# MOTOR.net
KiCad netlist of a schematic drawn in Altium Designer
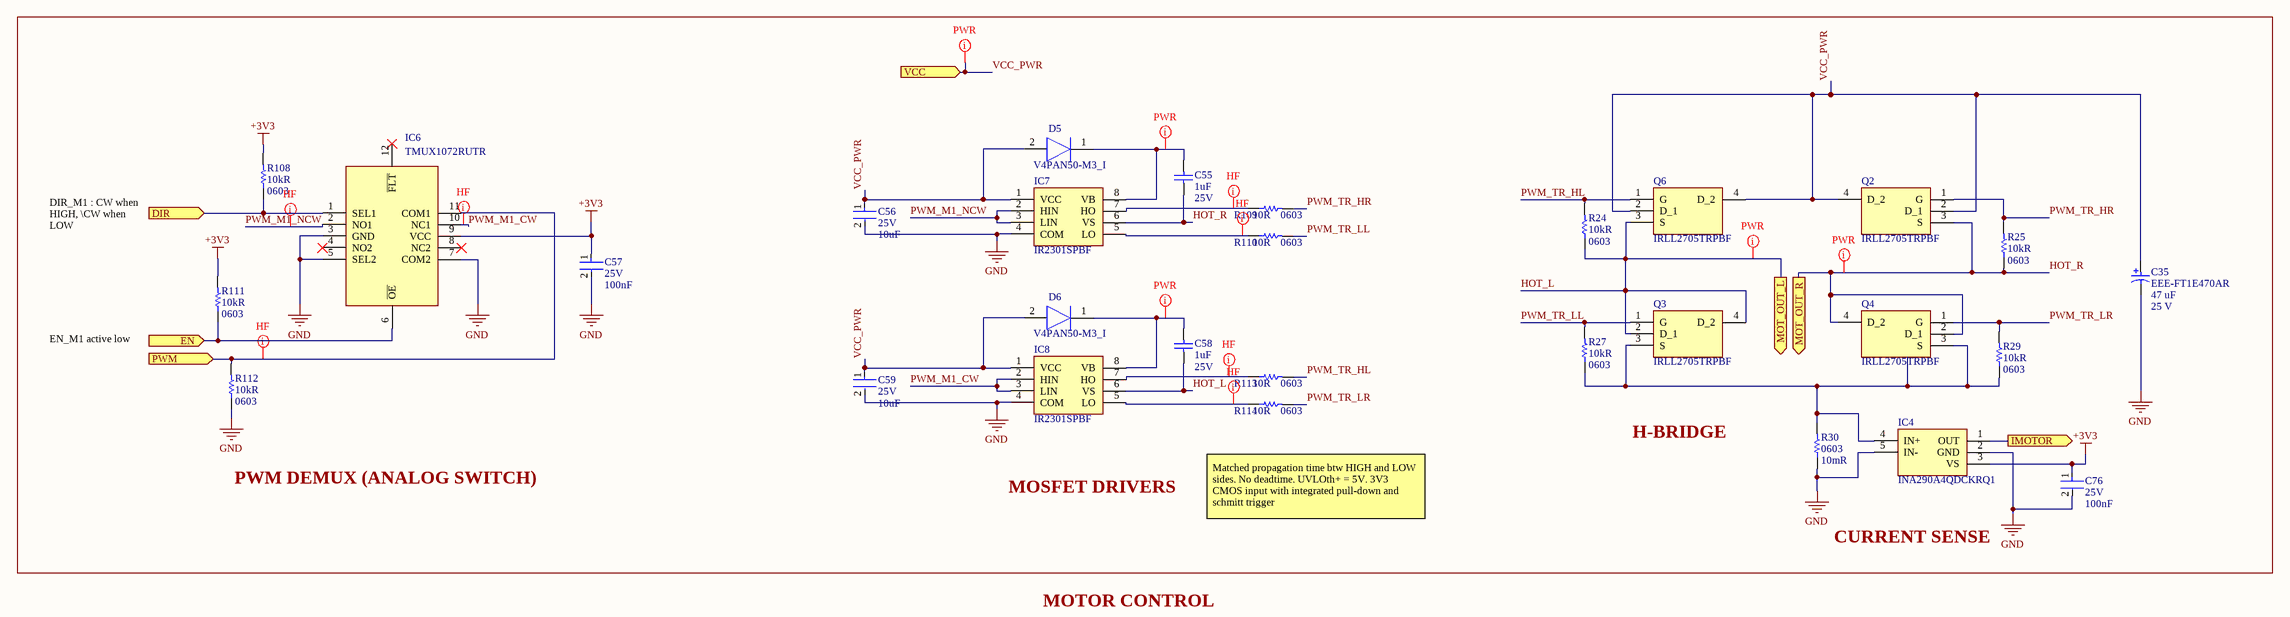
[diagram p0: MOTOR.SchDoc]

(export (version "E")
  (design (tool "Eeschema 10.0.6"))
  (components
    (comp (ref "C35")
      (value "EEE-FT1E470AR")
      (footprint "PNSC-FT-V-53x53-2_V")
      (fields
        (field (name "CAP.") "47 uF")
        (field (name "MANUFACTURER") "Panasonic")
        (field (name "RATED VOLTAGE") "25 V")
      )
      (libsource (lib "Altium Content Vault") (part "PNSC-CAP-P-2"))
    )
    (comp (ref "C55")
      (value "C0603C105K3PAC7867")
      (footprint "CAPC1608X90X35LL15T15")
      (fields
        (field (name "MANUFACTURER") "Kemet")
        (field (name "MANUFACTURER PART NUMBER") "C0603C105K3PACTU")
        (field (name "CAPACITANCE") "1uF")
        (field (name "TOLERANCE") "10%")
        (field (name "VOLTAGE RATING (DC)") "25V")
      )
      (libsource (lib "Altium Content Vault") (part "CAP"))
    )
    (comp (ref "C56")
      (value "C2012X5R1E106K125AB")
      (footprint "FP-C2012-125-0_2-IPC_B")
      (description "Multilayer Ceramic Capacitors 10μF ±10% 25V X5R SMD 0805")
      (fields
        (field (name "VOLTAGE") "25V")
        (field (name "VOLTAGE RATING (DC)") "25V")
        (field (name "TOLERANCE") "10%")
        (field (name "CAPACITANCE") "10uF")
      )
      (libsource (lib "Altium Content Vault") (part "b4654b650e69147ec39a6b967a45e02"))
    )
    (comp (ref "C57")
      (value "CGA3E2X7R1E104K080AA")
      (footprint "FP-CGA3E-0_3-0_1-MFG")
      (description "Cap Ceramic 100nF 25V X7R 10% Pad SMD 0603 +125°C Automotive T/R")
      (fields
        (field (name "VOLTAGE RATING (DC)") "25V")
        (field (name "CAPACITANCE") "100nF")
        (field (name "TOLERANCE") "10%")
        (field (name "MANUFACTURER") "TDK")
      )
      (libsource (lib "Altium Content Vault") (part "b4654b650e69147ec39a6b967a45e02"))
    )
    (comp (ref "C58")
      (value "C0603C105K3PAC7867")
      (footprint "CAPC1608X90X35LL15T15")
      (fields
        (field (name "MANUFACTURER") "Kemet")
        (field (name "MANUFACTURER PART NUMBER") "C0603C105K3PACTU")
        (field (name "CAPACITANCE") "1uF")
        (field (name "TOLERANCE") "10%")
        (field (name "VOLTAGE RATING (DC)") "25V")
      )
      (libsource (lib "Altium Content Vault") (part "CAP"))
    )
    (comp (ref "C59")
      (value "C2012X5R1E106K125AB")
      (footprint "FP-C2012-125-0_2-IPC_B")
      (description "Multilayer Ceramic Capacitors 10μF ±10% 25V X5R SMD 0805")
      (fields
        (field (name "VOLTAGE") "25V")
        (field (name "VOLTAGE RATING (DC)") "25V")
        (field (name "TOLERANCE") "10%")
        (field (name "CAPACITANCE") "10uF")
      )
      (libsource (lib "Altium Content Vault") (part "b4654b650e69147ec39a6b967a45e02"))
    )
    (comp (ref "C76")
      (value "CGA3E2X7R1E104K080AA")
      (footprint "FP-CGA3E-0_3-0_1-MFG")
      (description "Cap Ceramic 100nF 25V X7R 10% Pad SMD 0603 +125°C Automotive T/R")
      (fields
        (field (name "VOLTAGE RATING (DC)") "25V")
        (field (name "CAPACITANCE") "100nF")
        (field (name "TOLERANCE") "10%")
        (field (name "MANUFACTURER") "TDK")
      )
      (libsource (lib "Altium Content Vault") (part "b4654b650e69147ec39a6b967a45e02"))
    )
    (comp (ref "D5")
      (value "V4PAN50-M3_I")
      (footprint "SamacSys:V4PAN50M3I")
      (description "Diode")
      (fields
        (field (name "MANUFACTURER_PART_NUMBER") "V4PAN50-M3/I")
        (field (name "MOUSER PART NUMBER") "78-V4PAN50-M3/I")
      )
      (libsource (lib "*") (part "V4PAN50-M3_I"))
    )
    (comp (ref "D6")
      (value "V4PAN50-M3_I")
      (footprint "SamacSys:V4PAN50M3I")
      (description "Diode")
      (fields
        (field (name "MANUFACTURER_PART_NUMBER") "V4PAN50-M3/I")
        (field (name "MOUSER PART NUMBER") "78-V4PAN50-M3/I")
      )
      (libsource (lib "*") (part "V4PAN50-M3_I"))
    )
    (comp (ref "IC4")
      (value "INA290A4QDCKRQ1")
      (footprint "SamacSys:SOT65P210X110-5N")
      (description "Integrated Circuit")
      (fields (field (name "MOUSER PART NUMBER") "595-INA290A4QDCKRQ1"))
      (libsource (lib "*") (part "INA290A4QDCKRQ1"))
    )
    (comp (ref "IC6")
      (value "TMUX1072RUTR")
      (footprint "SamacSys:QFN40P170X200X55-12N")
      (description "Integrated Circuit")
      (fields (field (name "MOUSER PART NUMBER") "595-TMUX1072RUTR"))
      (libsource (lib "*") (part "TMUX1072RUTR"))
    )
    (comp (ref "IC7")
      (value "IR2301SPBF")
      (footprint "SamacSys:SOIC127P600X175-8N")
      (description "Integrated Circuit")
      (fields (field (name "MOUSER PART NUMBER") "942-IR2301SPBF"))
      (libsource (lib "*") (part "IR2301SPBF"))
    )
    (comp (ref "IC8")
      (value "IR2301SPBF")
      (footprint "SamacSys:SOIC127P600X175-8N")
      (description "Integrated Circuit")
      (fields (field (name "MOUSER PART NUMBER") "942-IR2301SPBF"))
      (libsource (lib "*") (part "IR2301SPBF"))
    )
    (comp (ref "Q2")
      (value "IRLL2705TRPBF")
      (footprint "SamacSys:SOT230P700X180-4N")
      (description "MOSFET (N-Channel)")
      (fields (field (name "MOUSER PART NUMBER") "942-IRLL2705TRPBF"))
      (libsource (lib "") (part "IRLL2705TRPBF_1"))
    )
    (comp (ref "Q3")
      (value "IRLL2705TRPBF")
      (footprint "SamacSys:SOT230P700X180-4N")
      (description "MOSFET (N-Channel)")
      (fields (field (name "MOUSER PART NUMBER") "942-IRLL2705TRPBF"))
      (libsource (lib "*") (part "IRLL2705TRPBF"))
    )
    (comp (ref "Q4")
      (value "IRLL2705TRPBF")
      (footprint "SamacSys:SOT230P700X180-4N")
      (description "MOSFET (N-Channel)")
      (fields (field (name "MOUSER PART NUMBER") "942-IRLL2705TRPBF"))
      (libsource (lib "") (part "IRLL2705TRPBF_1"))
    )
    (comp (ref "Q6")
      (value "IRLL2705TRPBF")
      (footprint "SamacSys:SOT230P700X180-4N")
      (description "MOSFET (N-Channel)")
      (fields (field (name "MOUSER PART NUMBER") "942-IRLL2705TRPBF"))
      (libsource (lib "*") (part "IRLL2705TRPBF"))
    )
    (comp (ref "R24")
      (value "ERJ3EKF1002V")
      (footprint "RESC1609X55X30LL15T15")
      (description "Chip Resistor, 10 KOhm, +/- 1%, 0.1 W, -55 to 155 degC, 0603 (1608 Metric), RoHS, Tape and Reel")
      (fields
        (field (name "RESISTANCE") "10kR")
        (field (name "CASE CODE (IMPERIAL)") "0603")
        (field (name "TOLERANCE") "1%")
        (field (name "MANUFACTURER") "Panasonic")
      )
      (libsource (lib "Altium Content Vault") (part "RES-2"))
    )
    (comp (ref "R25")
      (value "ERJ3EKF1002V")
      (footprint "RESC1609X55X30LL15T15")
      (description "Chip Resistor, 10 KOhm, +/- 1%, 0.1 W, -55 to 155 degC, 0603 (1608 Metric), RoHS, Tape and Reel")
      (fields
        (field (name "RESISTANCE") "10kR")
        (field (name "CASE CODE (IMPERIAL)") "0603")
        (field (name "TOLERANCE") "1%")
        (field (name "MANUFACTURER") "Panasonic")
      )
      (libsource (lib "Altium Content Vault") (part "RES-2"))
    )
    (comp (ref "R27")
      (value "ERJ3EKF1002V")
      (footprint "RESC1609X55X30LL15T15")
      (description "Chip Resistor, 10 KOhm, +/- 1%, 0.1 W, -55 to 155 degC, 0603 (1608 Metric), RoHS, Tape and Reel")
      (fields
        (field (name "RESISTANCE") "10kR")
        (field (name "CASE CODE (IMPERIAL)") "0603")
        (field (name "TOLERANCE") "1%")
        (field (name "MANUFACTURER") "Panasonic")
      )
      (libsource (lib "Altium Content Vault") (part "RES-2"))
    )
    (comp (ref "R29")
      (value "ERJ3EKF1002V")
      (footprint "RESC1609X55X30LL15T15")
      (description "Chip Resistor, 10 KOhm, +/- 1%, 0.1 W, -55 to 155 degC, 0603 (1608 Metric), RoHS, Tape and Reel")
      (fields
        (field (name "RESISTANCE") "10kR")
        (field (name "CASE CODE (IMPERIAL)") "0603")
        (field (name "TOLERANCE") "1%")
        (field (name "MANUFACTURER") "Panasonic")
      )
      (libsource (lib "Altium Content Vault") (part "RES-2"))
    )
    (comp (ref "R30")
      (value "WSL0603R0100FEA")
      (footprint "RESC1508X46X38ML25T25")
      (fields
        (field (name "MANUFACTURER") "Vishay Dale")
        (field (name "CASE CODE (IMPERIAL)") "0603")
        (field (name "TOLERANCE") "1%")
        (field (name "RESISTANCE") "10mR")
      )
      (libsource (lib "Altium Content Vault") (part "RES"))
    )
    (comp (ref "R108")
      (value "ERJ3EKF1002V")
      (footprint "RESC1609X55X30LL15T15")
      (description "Chip Resistor, 10 KOhm, +/- 1%, 0.1 W, -55 to 155 degC, 0603 (1608 Metric), RoHS, Tape and Reel")
      (fields
        (field (name "RESISTANCE") "10kR")
        (field (name "CASE CODE (IMPERIAL)") "0603")
        (field (name "TOLERANCE") "1%")
        (field (name "MANUFACTURER") "Panasonic")
      )
      (libsource (lib "Altium Content Vault") (part "RES-2"))
    )
    (comp (ref "R109")
      (value "RC0603FR-0710RL")
      (footprint "RESC1608X55X25NL10T15")
      (description "Chip Resistor, 10 Ohm, +/- 1%, 0.1 W, -55 to 155 degC, 0603 (1608 Metric), RoHS, Tape and Reel")
      (fields
        (field (name "MANUFACTURER") "Yageo")
        (field (name "CASE/PACKAGE") "0603")
        (field (name "RESISTANCE") "10R")
        (field (name "TOLERANCE") "1%")
      )
      (libsource (lib "Altium Content Vault") (part "RES-2"))
    )
    (comp (ref "R110")
      (value "RC0603FR-0710RL")
      (footprint "RESC1608X55X25NL10T15")
      (description "Chip Resistor, 10 Ohm, +/- 1%, 0.1 W, -55 to 155 degC, 0603 (1608 Metric), RoHS, Tape and Reel")
      (fields
        (field (name "MANUFACTURER") "Yageo")
        (field (name "CASE/PACKAGE") "0603")
        (field (name "RESISTANCE") "10R")
        (field (name "TOLERANCE") "1%")
      )
      (libsource (lib "Altium Content Vault") (part "RES-2"))
    )
    (comp (ref "R111")
      (value "ERJ3EKF1002V")
      (footprint "RESC1609X55X30LL15T15")
      (description "Chip Resistor, 10 KOhm, +/- 1%, 0.1 W, -55 to 155 degC, 0603 (1608 Metric), RoHS, Tape and Reel")
      (fields
        (field (name "RESISTANCE") "10kR")
        (field (name "CASE CODE (IMPERIAL)") "0603")
        (field (name "TOLERANCE") "1%")
        (field (name "MANUFACTURER") "Panasonic")
      )
      (libsource (lib "Altium Content Vault") (part "RES-2"))
    )
    (comp (ref "R112")
      (value "ERJ3EKF1002V")
      (footprint "RESC1609X55X30LL15T15")
      (description "Chip Resistor, 10 KOhm, +/- 1%, 0.1 W, -55 to 155 degC, 0603 (1608 Metric), RoHS, Tape and Reel")
      (fields
        (field (name "RESISTANCE") "10kR")
        (field (name "CASE CODE (IMPERIAL)") "0603")
        (field (name "TOLERANCE") "1%")
        (field (name "MANUFACTURER") "Panasonic")
      )
      (libsource (lib "Altium Content Vault") (part "RES-2"))
    )
    (comp (ref "R113")
      (value "RC0603FR-0710RL")
      (footprint "RESC1608X55X25NL10T15")
      (description "Chip Resistor, 10 Ohm, +/- 1%, 0.1 W, -55 to 155 degC, 0603 (1608 Metric), RoHS, Tape and Reel")
      (fields
        (field (name "MANUFACTURER") "Yageo")
        (field (name "CASE/PACKAGE") "0603")
        (field (name "RESISTANCE") "10R")
        (field (name "TOLERANCE") "1%")
      )
      (libsource (lib "Altium Content Vault") (part "RES-2"))
    )
    (comp (ref "R114")
      (value "RC0603FR-0710RL")
      (footprint "RESC1608X55X25NL10T15")
      (description "Chip Resistor, 10 Ohm, +/- 1%, 0.1 W, -55 to 155 degC, 0603 (1608 Metric), RoHS, Tape and Reel")
      (fields
        (field (name "MANUFACTURER") "Yageo")
        (field (name "CASE/PACKAGE") "0603")
        (field (name "RESISTANCE") "10R")
        (field (name "TOLERANCE") "1%")
      )
      (libsource (lib "Altium Content Vault") (part "RES-2"))
    )
  )
  (nets
    (net (code "1") (name "+3V3") (class "Default")
      (node (ref "C57") (pin "1") (pinfunction "1_1") (pintype "passive"))
      (node (ref "C76") (pin "1") (pinfunction "1_1") (pintype "passive"))
      (node (ref "IC4") (pin "3") (pinfunction "VS_3") (pintype "passive"))
      (node (ref "IC6") (pin "9") (pinfunction "VCC_9") (pintype "passive"))
      (node (ref "R108") (pin "2") (pinfunction "2_2") (pintype "passive"))
      (node (ref "R111") (pin "2") (pinfunction "2_2") (pintype "passive"))
    )
    (net (code "2") (name "/DIR") (class "Default")
      (node (ref "IC6") (pin "1") (pinfunction "SEL1_1") (pintype "passive"))
      (node (ref "R108") (pin "1") (pinfunction "1_1") (pintype "passive"))
    )
    (net (code "3") (name "/EN") (class "Default")
      (node (ref "IC6") (pin "6") (pinfunction "~{OE}_6") (pintype "passive"))
      (node (ref "R111") (pin "1") (pinfunction "1_1") (pintype "passive"))
    )
    (net (code "4") (name "/HOT_L") (class "Default")
      (node (ref "C58") (pin "1") (pinfunction "1_1") (pintype "passive"))
      (node (ref "IC8") (pin "6") (pinfunction "VS_6") (pintype "passive"))
      (node (ref "Q3") (pin "2") (pinfunction "D_1_2") (pintype "passive"))
      (node (ref "Q3") (pin "4") (pinfunction "D_2_4") (pintype "passive"))
      (node (ref "Q6") (pin "3") (pinfunction "S_3") (pintype "passive"))
      (node (ref "R24") (pin "1") (pinfunction "1_1") (pintype "passive"))
    )
    (net (code "5") (name "/HOT_R") (class "Default")
      (node (ref "C55") (pin "1") (pinfunction "1_1") (pintype "passive"))
      (node (ref "IC7") (pin "6") (pinfunction "VS_6") (pintype "passive"))
      (node (ref "Q2") (pin "3") (pinfunction "S_3") (pintype "passive"))
      (node (ref "Q4") (pin "2") (pinfunction "D_1_2") (pintype "passive"))
      (node (ref "Q4") (pin "4") (pinfunction "D_2_4") (pintype "passive"))
      (node (ref "R25") (pin "1") (pinfunction "1_1") (pintype "passive"))
    )
    (net (code "6") (name "/IMOTOR") (class "Default")
      (node (ref "IC4") (pin "1") (pinfunction "OUT_1") (pintype "passive"))
    )
    (net (code "7") (name "/PWM") (class "Default")
      (node (ref "IC6") (pin "11") (pinfunction "COM1_11") (pintype "passive"))
      (node (ref "R112") (pin "2") (pinfunction "2_2") (pintype "passive"))
    )
    (net (code "8") (name "/PWM_M1_CW") (class "Default")
      (node (ref "IC6") (pin "10") (pinfunction "NC1_10") (pintype "passive"))
      (node (ref "IC8") (pin "2") (pinfunction "HIN_2") (pintype "passive"))
      (node (ref "IC8") (pin "3") (pinfunction "LIN_3") (pintype "passive"))
    )
    (net (code "9") (name "/PWM_M1_NCW") (class "Default")
      (node (ref "IC6") (pin "2") (pinfunction "NO1_2") (pintype "passive"))
      (node (ref "IC7") (pin "2") (pinfunction "HIN_2") (pintype "passive"))
      (node (ref "IC7") (pin "3") (pinfunction "LIN_3") (pintype "passive"))
    )
    (net (code "10") (name "/PWM_TR_HL") (class "Default")
      (node (ref "Q6") (pin "1") (pinfunction "G_1") (pintype "passive"))
      (node (ref "R113") (pin "2") (pinfunction "2_2") (pintype "passive"))
      (node (ref "R24") (pin "2") (pinfunction "2_2") (pintype "passive"))
    )
    (net (code "11") (name "/PWM_TR_HR") (class "Default")
      (node (ref "Q2") (pin "1") (pinfunction "G_1") (pintype "passive"))
      (node (ref "R109") (pin "2") (pinfunction "2_2") (pintype "passive"))
      (node (ref "R25") (pin "2") (pinfunction "2_2") (pintype "passive"))
    )
    (net (code "12") (name "/PWM_TR_LL") (class "Default")
      (node (ref "Q3") (pin "1") (pinfunction "G_1") (pintype "passive"))
      (node (ref "R110") (pin "2") (pinfunction "2_2") (pintype "passive"))
      (node (ref "R27") (pin "2") (pinfunction "2_2") (pintype "passive"))
    )
    (net (code "13") (name "/PWM_TR_LR") (class "Default")
      (node (ref "Q4") (pin "1") (pinfunction "G_1") (pintype "passive"))
      (node (ref "R114") (pin "2") (pinfunction "2_2") (pintype "passive"))
      (node (ref "R29") (pin "2") (pinfunction "2_2") (pintype "passive"))
    )
    (net (code "14") (name "/VCC_PWR") (class "Default")
      (node (ref "C35") (pin "1") (pinfunction "1_1") (pintype "passive"))
      (node (ref "C56") (pin "1") (pinfunction "1_1") (pintype "passive"))
      (node (ref "C59") (pin "1") (pinfunction "1_1") (pintype "passive"))
      (node (ref "D5") (pin "2") (pinfunction "A_2") (pintype "passive"))
      (node (ref "D6") (pin "2") (pinfunction "A_2") (pintype "passive"))
      (node (ref "IC7") (pin "1") (pinfunction "VCC_1") (pintype "passive"))
      (node (ref "IC8") (pin "1") (pinfunction "VCC_1") (pintype "passive"))
      (node (ref "Q2") (pin "2") (pinfunction "D_1_2") (pintype "passive"))
      (node (ref "Q2") (pin "4") (pinfunction "D_2_4") (pintype "passive"))
      (node (ref "Q6") (pin "2") (pinfunction "D_1_2") (pintype "passive"))
      (node (ref "Q6") (pin "4") (pinfunction "D_2_4") (pintype "passive"))
    )
    (net (code "15") (name "GND") (class "Default")
      (node (ref "C35") (pin "2") (pinfunction "2_2") (pintype "passive"))
      (node (ref "C56") (pin "2") (pinfunction "2_2") (pintype "passive"))
      (node (ref "C57") (pin "2") (pinfunction "2_2") (pintype "passive"))
      (node (ref "C59") (pin "2") (pinfunction "2_2") (pintype "passive"))
      (node (ref "C76") (pin "2") (pinfunction "2_2") (pintype "passive"))
      (node (ref "IC4") (pin "2") (pinfunction "GND_2") (pintype "passive"))
      (node (ref "IC4") (pin "5") (pinfunction "IN-_5") (pintype "passive"))
      (node (ref "IC6") (pin "3") (pinfunction "GND_3") (pintype "passive"))
      (node (ref "IC6") (pin "5") (pinfunction "SEL2_5") (pintype "passive"))
      (node (ref "IC6") (pin "7") (pinfunction "COM2_7") (pintype "passive"))
      (node (ref "IC7") (pin "4") (pinfunction "COM_4") (pintype "passive"))
      (node (ref "IC8") (pin "4") (pinfunction "COM_4") (pintype "passive"))
      (node (ref "R112") (pin "1") (pinfunction "1_1") (pintype "passive"))
      (node (ref "R30") (pin "1") (pinfunction "1_1") (pintype "passive"))
    )
    (net (code "16") (name "Net-(D5-K)") (class "Default")
      (node (ref "C55") (pin "2") (pinfunction "2_2") (pintype "passive"))
      (node (ref "D5") (pin "1") (pinfunction "K_1") (pintype "passive"))
      (node (ref "IC7") (pin "8") (pinfunction "VB_8") (pintype "passive"))
    )
    (net (code "17") (name "Net-(D6-K)") (class "Default")
      (node (ref "C58") (pin "2") (pinfunction "2_2") (pintype "passive"))
      (node (ref "D6") (pin "1") (pinfunction "K_1") (pintype "passive"))
      (node (ref "IC8") (pin "8") (pinfunction "VB_8") (pintype "passive"))
    )
    (net (code "18") (name "Net-(IC4-IN+)") (class "Default")
      (node (ref "IC4") (pin "4") (pinfunction "IN+_4") (pintype "passive"))
      (node (ref "Q3") (pin "3") (pinfunction "S_3") (pintype "passive"))
      (node (ref "Q4") (pin "3") (pinfunction "S_3") (pintype "passive"))
      (node (ref "R27") (pin "1") (pinfunction "1_1") (pintype "passive"))
      (node (ref "R29") (pin "1") (pinfunction "1_1") (pintype "passive"))
      (node (ref "R30") (pin "2") (pinfunction "2_2") (pintype "passive"))
    )
    (net (code "19") (name "Net-(IC7-HO)") (class "Default")
      (node (ref "IC7") (pin "7") (pinfunction "HO_7") (pintype "passive"))
      (node (ref "R109") (pin "1") (pinfunction "1_1") (pintype "passive"))
    )
    (net (code "20") (name "Net-(IC7-LO)") (class "Default")
      (node (ref "IC7") (pin "5") (pinfunction "LO_5") (pintype "passive"))
      (node (ref "R110") (pin "1") (pinfunction "1_1") (pintype "passive"))
    )
    (net (code "21") (name "Net-(IC8-HO)") (class "Default")
      (node (ref "IC8") (pin "7") (pinfunction "HO_7") (pintype "passive"))
      (node (ref "R113") (pin "1") (pinfunction "1_1") (pintype "passive"))
    )
    (net (code "22") (name "Net-(IC8-LO)") (class "Default")
      (node (ref "IC8") (pin "5") (pinfunction "LO_5") (pintype "passive"))
      (node (ref "R114") (pin "1") (pinfunction "1_1") (pintype "passive"))
    )
    (net (code "23") (name "unconnected-(IC6-NC2-Pad8)") (class "Default")
      (node (ref "IC6") (pin "8") (pinfunction "NC2_8") (pintype "passive+no_connect"))
    )
    (net (code "24") (name "unconnected-(IC6-NO2-Pad4)") (class "Default")
      (node (ref "IC6") (pin "4") (pinfunction "NO2_4") (pintype "passive+no_connect"))
    )
    (net (code "25") (name "unconnected-(IC6-~{FLT}-Pad12)") (class "Default")
      (node (ref "IC6") (pin "12") (pinfunction "~{FLT}_12") (pintype "passive+no_connect"))
    )
  )
)
